# ESP8266_Core.net
KiCad netlist of a schematic drawn in Altium Designer
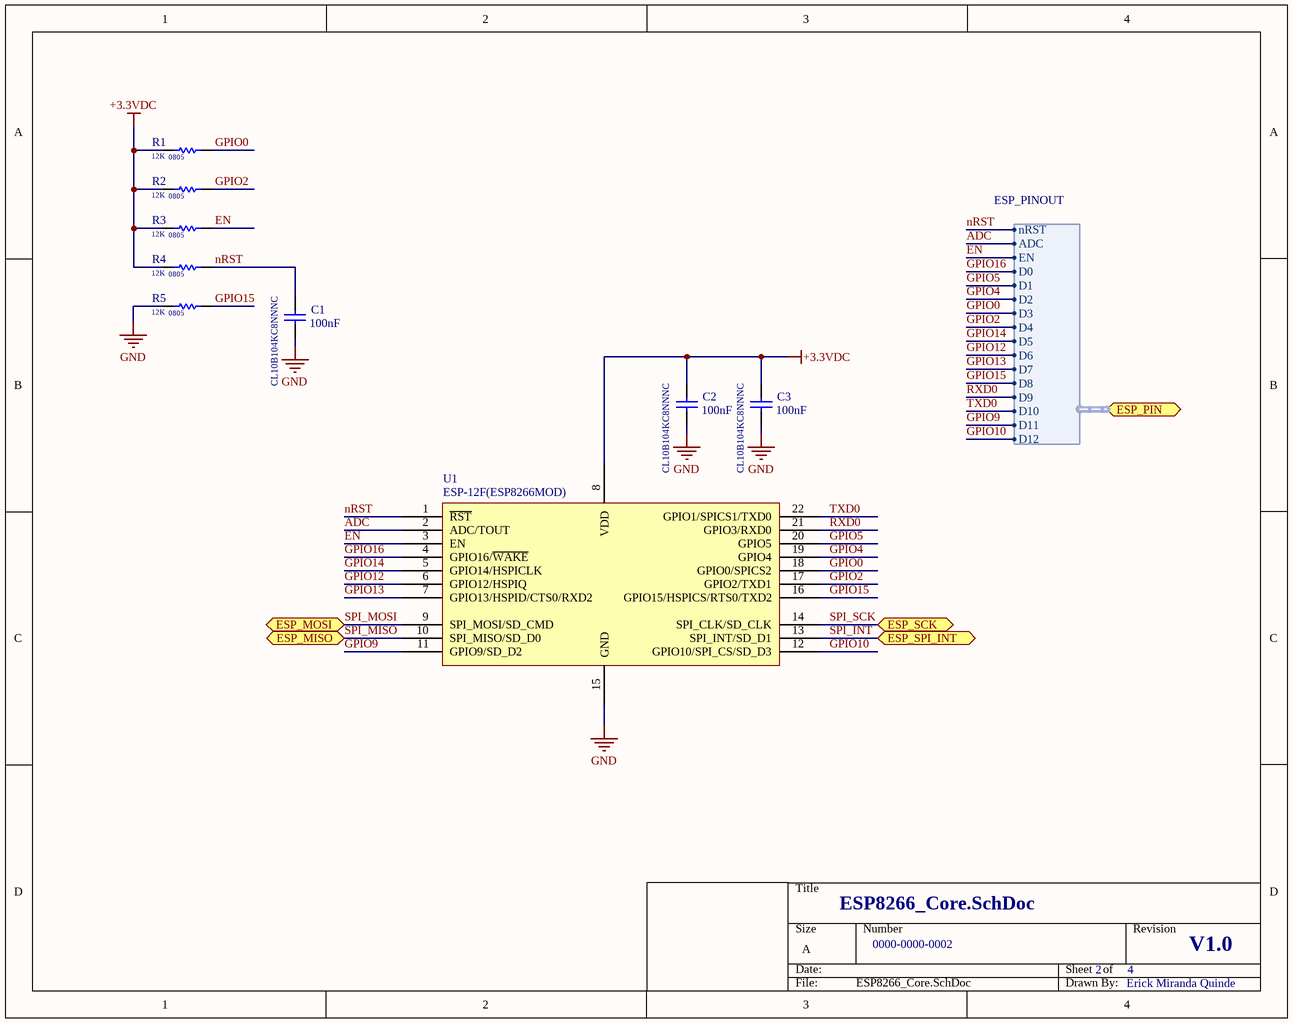
[diagram p0: ESP8266_Core.SchDoc]

(export (version "E")
  (design (tool "Eeschema 10.0.6"))
  (components
    (comp (ref "C1")
      (value "CL10B104KC8NNNC")
      (footprint "C0603C104K5RACTU")
      (fields (field (name "ALTIUM_VALUE") "100nF") (field (name "LCSC PART") "C15725"))
      (libsource (lib "IDETEC LIB") (part "Cap 100nF (0603)"))
    )
    (comp (ref "C2")
      (value "CL10B104KC8NNNC")
      (footprint "C0603C104K5RACTU")
      (fields (field (name "ALTIUM_VALUE") "100nF") (field (name "LCSC PART") "C15725"))
      (libsource (lib "IDETEC LIB") (part "Cap 100nF (0603)"))
    )
    (comp (ref "C3")
      (value "CL10B104KC8NNNC")
      (footprint "C0603C104K5RACTU")
      (fields (field (name "ALTIUM_VALUE") "100nF") (field (name "LCSC PART") "C15725"))
      (libsource (lib "IDETEC LIB") (part "Cap 100nF (0603)"))
    )
    (comp (ref "R1")
      (value "12K")
      (footprint "RES-0805")
      (description "Resistor")
      (fields
        (field (name "PACKAGE") "0805")
        (field (name "LCSC PART") "C336850")
        (field (name "Comment") "ERJ6RBD1202V")
        (field (name "PUBLISHER") "Altium Limited")
      )
      (libsource (lib "IDETEC LIB") (part "Resistor"))
    )
    (comp (ref "R2")
      (value "12K")
      (footprint "RES-0805")
      (description "Resistor")
      (fields
        (field (name "PACKAGE") "0805")
        (field (name "LCSC PART") "C336850")
        (field (name "Comment") "ERJ6RBD1202V")
        (field (name "PUBLISHER") "Altium Limited")
      )
      (libsource (lib "IDETEC LIB") (part "Resistor"))
    )
    (comp (ref "R3")
      (value "12K")
      (footprint "RES-0805")
      (description "Resistor")
      (fields
        (field (name "PACKAGE") "0805")
        (field (name "LCSC PART") "C336850")
        (field (name "Comment") "ERJ6RBD1202V")
        (field (name "PUBLISHER") "Altium Limited")
      )
      (libsource (lib "IDETEC LIB") (part "Resistor"))
    )
    (comp (ref "R4")
      (value "12K")
      (footprint "RES-0805")
      (description "Resistor")
      (fields
        (field (name "PACKAGE") "0805")
        (field (name "LCSC PART") "C336850")
        (field (name "Comment") "ERJ6RBD1202V")
        (field (name "PUBLISHER") "Altium Limited")
      )
      (libsource (lib "IDETEC LIB") (part "Resistor"))
    )
    (comp (ref "R5")
      (value "12K")
      (footprint "RES-0805")
      (description "Resistor")
      (fields
        (field (name "PACKAGE") "0805")
        (field (name "LCSC PART") "C336850")
        (field (name "Comment") "ERJ6RBD1202V")
        (field (name "PUBLISHER") "Altium Limited")
      )
      (libsource (lib "IDETEC LIB") (part "Resistor"))
    )
    (comp (ref "U1")
      (value "ESP-12F(ESP8266MOD)")
      (footprint "ESP-12E&F Module")
      (description "ESP-12E&F Module")
      (fields (field (name "LCSC PART") "C82891"))
      (libsource (lib "ESP-12E&F Module") (part "ESP-12E&F Module"))
    )
  )
  (nets
    (net (code "2") (name "+3.3VDC") (class "Default")
      (node (ref "C2") (pin "2") (pinfunction "2_2") (pintype "passive"))
      (node (ref "C3") (pin "2") (pinfunction "2_2") (pintype "passive"))
      (node (ref "R1") (pin "1") (pinfunction "1_1") (pintype "passive"))
      (node (ref "R2") (pin "1") (pinfunction "1_1") (pintype "passive"))
      (node (ref "R3") (pin "1") (pinfunction "1_1") (pintype "passive"))
      (node (ref "R4") (pin "1") (pinfunction "1_1") (pintype "passive"))
      (node (ref "U1") (pin "8") (pinfunction "VDD_8") (pintype "passive"))
    )
    (net (code "3") (name "/ADC") (class "Default")
      (node (ref "U1") (pin "2") (pinfunction "ADC/TOUT_2") (pintype "passive"))
    )
    (net (code "4") (name "/EN") (class "Default")
      (node (ref "R3") (pin "2") (pinfunction "2_2") (pintype "passive"))
      (node (ref "U1") (pin "3") (pinfunction "EN_3") (pintype "passive"))
    )
    (net (code "5") (name "/GPIO0") (class "Default")
      (node (ref "R1") (pin "2") (pinfunction "2_2") (pintype "passive"))
      (node (ref "U1") (pin "18") (pinfunction "GPIO0/SPICS2_18") (pintype "passive"))
    )
    (net (code "6") (name "/GPIO2") (class "Default")
      (node (ref "R2") (pin "2") (pinfunction "2_2") (pintype "passive"))
      (node (ref "U1") (pin "17") (pinfunction "GPIO2/TXD1_17") (pintype "passive"))
    )
    (net (code "7") (name "/GPIO4") (class "Default")
      (node (ref "U1") (pin "19") (pinfunction "GPIO4_19") (pintype "passive"))
    )
    (net (code "8") (name "/GPIO5") (class "Default")
      (node (ref "U1") (pin "20") (pinfunction "GPIO5_20") (pintype "passive"))
    )
    (net (code "9") (name "/GPIO9") (class "Default")
      (node (ref "U1") (pin "11") (pinfunction "GPIO9/SD_D2_11") (pintype "passive"))
    )
    (net (code "10") (name "/GPIO10") (class "Default")
      (node (ref "U1") (pin "12") (pinfunction "GPIO10/SPI_CS/SD_D3_12") (pintype "passive"))
    )
    (net (code "11") (name "/GPIO12") (class "Default")
      (node (ref "U1") (pin "6") (pinfunction "GPIO12/HSPIQ_6") (pintype "passive"))
    )
    (net (code "12") (name "/GPIO13") (class "Default")
      (node (ref "U1") (pin "7") (pinfunction "GPIO13/HSPID/CTS0/RXD2_7") (pintype "passive"))
    )
    (net (code "13") (name "/GPIO14") (class "Default")
      (node (ref "U1") (pin "5") (pinfunction "GPIO14/HSPICLK_5") (pintype "passive"))
    )
    (net (code "14") (name "/GPIO15") (class "Default")
      (node (ref "R5") (pin "2") (pinfunction "2_2") (pintype "passive"))
      (node (ref "U1") (pin "16") (pinfunction "GPIO15/HSPICS/RTS0/TXD2_16") (pintype "passive"))
    )
    (net (code "15") (name "/GPIO16") (class "Default")
      (node (ref "U1") (pin "4") (pinfunction "GPIO16/~{WAKE}_4") (pintype "passive"))
    )
    (net (code "16") (name "/RXD0") (class "Default")
      (node (ref "U1") (pin "21") (pinfunction "GPIO3/RXD0_21") (pintype "passive"))
    )
    (net (code "17") (name "/SPI_INT") (class "Default")
      (node (ref "U1") (pin "13") (pinfunction "SPI_INT/SD_D1_13") (pintype "passive"))
    )
    (net (code "18") (name "/SPI_MISO") (class "Default")
      (node (ref "U1") (pin "10") (pinfunction "SPI_MISO/SD_D0_10") (pintype "passive"))
    )
    (net (code "19") (name "/SPI_MOSI") (class "Default")
      (node (ref "U1") (pin "9") (pinfunction "SPI_MOSI/SD_CMD_9") (pintype "passive"))
    )
    (net (code "20") (name "/SPI_SCK") (class "Default")
      (node (ref "U1") (pin "14") (pinfunction "SPI_CLK/SD_CLK_14") (pintype "passive"))
    )
    (net (code "21") (name "/TXD0") (class "Default")
      (node (ref "U1") (pin "22") (pinfunction "GPIO1/SPICS1/TXD0_22") (pintype "passive"))
    )
    (net (code "22") (name "/nRST") (class "Default")
      (node (ref "C1") (pin "2") (pinfunction "2_2") (pintype "passive"))
      (node (ref "R4") (pin "2") (pinfunction "2_2") (pintype "passive"))
      (node (ref "U1") (pin "1") (pinfunction "~{RST}_1") (pintype "passive"))
    )
    (net (code "24") (name "GND") (class "Default")
      (node (ref "C1") (pin "1") (pinfunction "1_1") (pintype "passive"))
      (node (ref "C2") (pin "1") (pinfunction "1_1") (pintype "passive"))
      (node (ref "C3") (pin "1") (pinfunction "1_1") (pintype "passive"))
      (node (ref "R5") (pin "1") (pinfunction "1_1") (pintype "passive"))
      (node (ref "U1") (pin "15") (pinfunction "GND_15") (pintype "passive"))
    )
  )
)
